# Zero_Crossing.net
KiCad netlist of a schematic drawn in Altium Designer
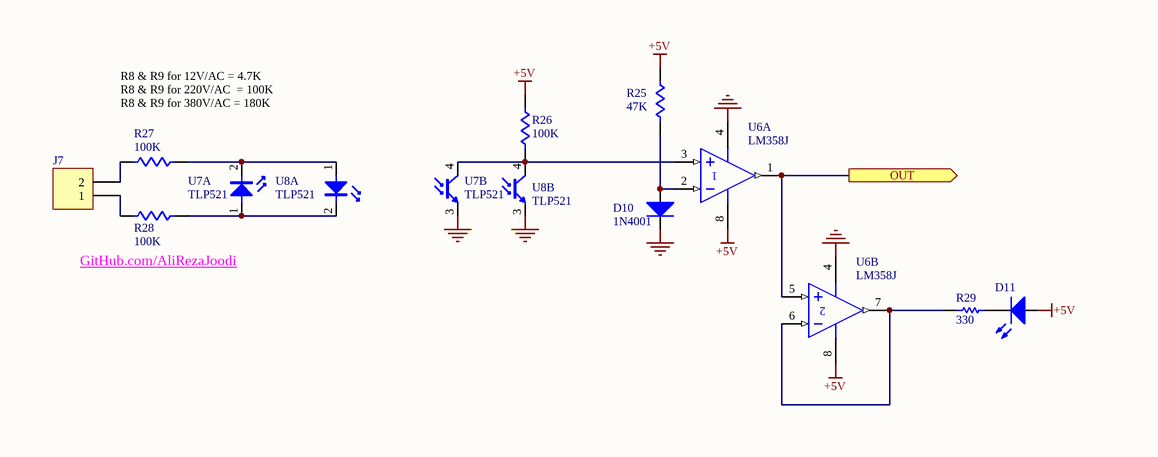
[diagram p0: Zero Crossing.SchDoc]

(export (version "E")
  (design (tool "Eeschema 10.0.6"))
  (components
    (comp (ref "D10")
      (value "1N4001")
      (footprint "DIODE-0.4")
      (description "Default Diode")
      (fields (field (name "MANUFACTURER") "Generic Components") (field (name "PUBLISHER") "Altium Limited"))
      (libsource (lib "Miscellaneous Devices") (part "Diode"))
    )
    (comp (ref "D11")
      (value "LED")
      (footprint "LED-5mm_Red")
      (description "Typical INFRARED GaAs LED")
      (fields (field (name "MANUFACTURER") "Generic Components") (field (name "PUBLISHER") "Altium Limited"))
      (libsource (lib "Miscellaneous Devices") (part "LED"))
    )
    (comp (ref "J7")
      (value "Header 2")
      (footprint "Fonics_2PIN_1")
      (description "Header, 2-Pin")
      (fields (field (name "PUBLISHER") "Altium Limited"))
      (libsource (lib "Miscellaneous Connectors") (part "Header 2"))
    )
    (comp (ref "R25")
      (value "47K")
      (footprint "AXIAL-0.4")
      (description "Resistor")
      (fields
        (field (name "MANUFACTURER") "Generic Components")
        (field (name "Comment") "Res1")
        (field (name "PUBLISHER") "Altium Limited")
      )
      (libsource (lib "") (part "Res1_1"))
    )
    (comp (ref "R26")
      (value "100K")
      (footprint "AXIAL-0.4")
      (description "Resistor")
      (fields
        (field (name "MANUFACTURER") "Generic Components")
        (field (name "Comment") "Res1")
        (field (name "PUBLISHER") "Altium Limited")
      )
      (libsource (lib "") (part "Res1_1"))
    )
    (comp (ref "R27")
      (value "100K")
      (footprint "AXIAL-0.4")
      (description "Resistor")
      (fields
        (field (name "MANUFACTURER") "Generic Components")
        (field (name "Comment") "Res1")
        (field (name "PUBLISHER") "Altium Limited")
      )
      (libsource (lib "") (part "Res1_1"))
    )
    (comp (ref "R28")
      (value "100K")
      (footprint "AXIAL-0.4")
      (description "Resistor")
      (fields
        (field (name "MANUFACTURER") "Generic Components")
        (field (name "Comment") "Res1")
        (field (name "PUBLISHER") "Altium Limited")
      )
      (libsource (lib "") (part "Res1_1"))
    )
    (comp (ref "R29")
      (value "330")
      (footprint "AXIAL-0.4")
      (description "Resistor")
      (fields (field (name "MANUFACTURER") "Generic Components") (field (name "PUBLISHER") "Altium Limited"))
      (libsource (lib "Miscellaneous Devices") (part "Res1"))
    )
    (comp (ref "U6")
      (value "LM358J")
      (footprint "693-02")
      (description "Dual Low-Power Operational Amplifier")
      (fields (field (name "PUBLISHER") "Altium Limited"))
      (libsource (lib "Motorola Amplifier Operational Amplifier") (part "LM358J"))
    )
    (comp (ref "U7")
      (value "TLP521")
      (footprint "DIP-4")
      (fields (field (name "Comment") "Optoisolator") (field (name "PUBLISHER") "Altium Limited"))
      (libsource (lib "my Libraries") (part "Optoisolator"))
    )
    (comp (ref "U8")
      (value "TLP521")
      (footprint "DIP-4")
      (fields (field (name "Comment") "Optoisolator") (field (name "PUBLISHER") "Altium Limited"))
      (libsource (lib "my Libraries") (part "Optoisolator"))
    )
  )
  (nets
    (net (code "1") (name "+5V") (class "Default")
      (node (ref "D11") (pin "1") (pinfunction "A_1") (pintype "passive"))
      (node (ref "R25") (pin "1") (pinfunction "1_1") (pintype "passive"))
      (node (ref "R26") (pin "1") (pinfunction "1_1") (pintype "passive"))
      (node (ref "U6") (pin "8") (pinfunction "V+_8") (pintype "power_in"))
    )
    (net (code "2") (name "/OUT") (class "Default")
      (node (ref "U6") (pin "1") (pinfunction "OUT_1") (pintype "output"))
      (node (ref "U6") (pin "5") (pinfunction "IN+_5") (pintype "input"))
    )
    (net (code "3") (name "GND") (class "Default")
      (node (ref "D10") (pin "2") (pinfunction "K_2") (pintype "passive"))
      (node (ref "U6") (pin "4") (pinfunction "V-_4") (pintype "power_in"))
      (node (ref "U7") (pin "3") (pinfunction "E_3") (pintype "passive"))
      (node (ref "U8") (pin "3") (pinfunction "E_3") (pintype "passive"))
    )
    (net (code "4") (name "Net-(D10-A)") (class "Default")
      (node (ref "D10") (pin "1") (pinfunction "A_1") (pintype "passive"))
      (node (ref "R25") (pin "2") (pinfunction "2_2") (pintype "passive"))
      (node (ref "U6") (pin "2") (pinfunction "IN-_2") (pintype "input"))
    )
    (net (code "5") (name "Net-(D11-K)") (class "Default")
      (node (ref "D11") (pin "2") (pinfunction "K_2") (pintype "passive"))
      (node (ref "R29") (pin "1") (pinfunction "1_1") (pintype "passive"))
    )
    (net (code "6") (name "Net-(J7-Pad1)") (class "Default")
      (node (ref "J7") (pin "1") (pinfunction "1_1") (pintype "passive"))
      (node (ref "R28") (pin "1") (pinfunction "1_1") (pintype "passive"))
    )
    (net (code "7") (name "Net-(J7-Pad2)") (class "Default")
      (node (ref "J7") (pin "2") (pinfunction "2_2") (pintype "passive"))
      (node (ref "R27") (pin "1") (pinfunction "1_1") (pintype "passive"))
    )
    (net (code "8") (name "Net-(U6A-IN+)") (class "Default")
      (node (ref "R26") (pin "2") (pinfunction "2_2") (pintype "passive"))
      (node (ref "U6") (pin "3") (pinfunction "IN+_3") (pintype "input"))
      (node (ref "U7") (pin "4") (pinfunction "C_4") (pintype "passive"))
      (node (ref "U8") (pin "4") (pinfunction "C_4") (pintype "passive"))
    )
    (net (code "9") (name "Net-(U6B-IN-)") (class "Default")
      (node (ref "R29") (pin "2") (pinfunction "2_2") (pintype "passive"))
      (node (ref "U6") (pin "6") (pinfunction "IN-_6") (pintype "input"))
      (node (ref "U6") (pin "7") (pinfunction "OUT_7") (pintype "output"))
    )
    (net (code "10") (name "Net-(U7A-A)") (class "Default")
      (node (ref "R28") (pin "2") (pinfunction "2_2") (pintype "passive"))
      (node (ref "U7") (pin "1") (pinfunction "A_1") (pintype "power_in"))
      (node (ref "U8") (pin "2") (pinfunction "K_2") (pintype "power_in"))
    )
    (net (code "11") (name "Net-(U7A-K)") (class "Default")
      (node (ref "R27") (pin "2") (pinfunction "2_2") (pintype "passive"))
      (node (ref "U7") (pin "2") (pinfunction "K_2") (pintype "power_in"))
      (node (ref "U8") (pin "1") (pinfunction "A_1") (pintype "power_in"))
    )
  )
)
